# pcb-lt3032.net
KiCad netlist of a schematic drawn in EAGLE
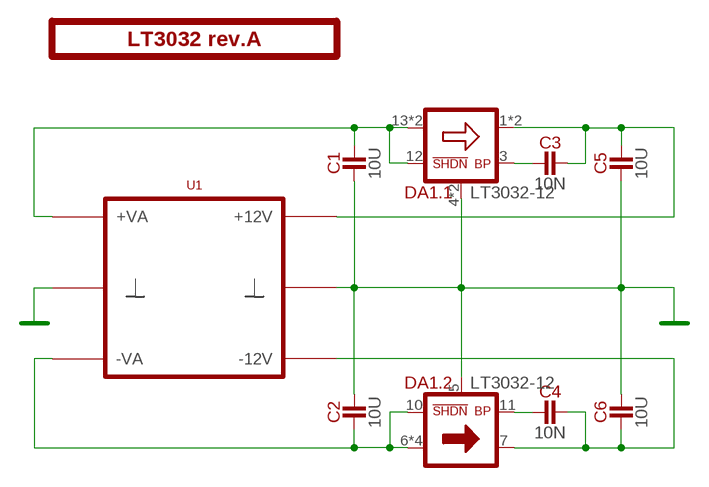
[diagram p0: schematic, sheet 1]

(export (version "E")
  (design (tool "Eeschema 10.0.6"))
  (components
    (comp (ref "C1")
      (value "10U")
      (footprint "eagle-import:C-1206")
      (libsource (lib "eagle-import") (part "?10U"))
    )
    (comp (ref "C2")
      (value "10U")
      (footprint "eagle-import:C-1206")
      (libsource (lib "eagle-import") (part "?10U"))
    )
    (comp (ref "C3")
      (value "10N")
      (footprint "eagle-import:C-0805")
      (libsource (lib "eagle-import") (part "?10N"))
    )
    (comp (ref "C4")
      (value "10N")
      (footprint "eagle-import:C-0805")
      (libsource (lib "eagle-import") (part "?10N"))
    )
    (comp (ref "C5")
      (value "10U")
      (footprint "eagle-import:C-1206")
      (libsource (lib "eagle-import") (part "?10U"))
    )
    (comp (ref "C6")
      (value "10U")
      (footprint "eagle-import:C-1206")
      (libsource (lib "eagle-import") (part "?10U"))
    )
    (comp (ref "DA1")
      (value "LT3032-12")
      (footprint "eagle-import:DE14MA")
      (libsource (lib "eagle-import") (part "LT3032-12"))
    )
    (comp (ref "PCB1")
      (value "LT3032 rev.A")
      (footprint "eagle-import:F-LOGO")
      (libsource (lib "eagle-import") (part "GENERIC-LOGO"))
    )
    (comp (ref "U1")
      (value "F-DUAL-SUPPLY-BOARD")
      (footprint "eagle-import:F-DIP8-HEATSINK-NOSILK")
      (libsource (lib "eagle-import") (part "F-DUAL-SUPPLY-BOARD"))
    )
  )
  (nets
    (net (code "1") (name "GND") (class "Default")
      (node (ref "C1") (pin "1") (pinfunction "1_1") (pintype "passive"))
      (node (ref "C2") (pin "2") (pinfunction "2_2") (pintype "passive"))
      (node (ref "C5") (pin "1") (pinfunction "1_1") (pintype "passive"))
      (node (ref "C6") (pin "2") (pinfunction "2_2") (pintype "passive"))
      (node (ref "DA1") (pin "15") (pinfunction "GND_15") (pintype "passive"))
      (node (ref "DA1") (pin "4") (pinfunction "GND_4") (pintype "passive"))
      (node (ref "DA1") (pin "5") (pinfunction "GND_5") (pintype "passive"))
      (node (ref "U1") (pin "2") (pinfunction "GND1_2") (pintype "bidirectional"))
      (node (ref "U1") (pin "3") (pinfunction "GND1_3") (pintype "bidirectional"))
      (node (ref "U1") (pin "6") (pinfunction "GND_6") (pintype "bidirectional"))
      (node (ref "U1") (pin "7") (pinfunction "GND_7") (pintype "bidirectional"))
      (node (ref "U1") (pin "P$1") (pinfunction "GND_P$1") (pintype "bidirectional"))
    )
    (net (code "2") (name "Net-(DA1A-BYP)") (class "Default")
      (node (ref "C3") (pin "1") (pinfunction "1_1") (pintype "passive"))
      (node (ref "DA1") (pin "3") (pinfunction "BYP_3") (pintype "passive"))
    )
    (net (code "3") (name "Net-(DA1A-~{SHDN})") (class "Default")
      (node (ref "C1") (pin "2") (pinfunction "2_2") (pintype "passive"))
      (node (ref "DA1") (pin "12") (pinfunction "~{SHDN}_12") (pintype "passive"))
      (node (ref "DA1") (pin "13") (pinfunction "IN_13") (pintype "passive"))
      (node (ref "DA1") (pin "14") (pinfunction "IN_14") (pintype "passive"))
      (node (ref "U1") (pin "1") (pinfunction "P+VA_1") (pintype "bidirectional"))
    )
    (net (code "4") (name "Net-(DA1B-BYP)") (class "Default")
      (node (ref "C4") (pin "1") (pinfunction "1_1") (pintype "passive"))
      (node (ref "DA1") (pin "11") (pinfunction "BYP_11") (pintype "passive"))
    )
    (net (code "5") (name "Net-(DA1B-OUT)") (class "Default")
      (node (ref "C4") (pin "2") (pinfunction "2_2") (pintype "passive"))
      (node (ref "C6") (pin "1") (pinfunction "1_1") (pintype "passive"))
      (node (ref "DA1") (pin "7") (pinfunction "OUT_7") (pintype "passive"))
      (node (ref "U1") (pin "5") (pinfunction "P-12V_5") (pintype "bidirectional"))
    )
    (net (code "6") (name "Net-(DA1B-~{SHDN})") (class "Default")
      (node (ref "C2") (pin "1") (pinfunction "1_1") (pintype "passive"))
      (node (ref "DA1") (pin "10") (pinfunction "~{SHDN}_10") (pintype "passive"))
      (node (ref "DA1") (pin "16") (pinfunction "IN_16") (pintype "passive"))
      (node (ref "DA1") (pin "6") (pinfunction "IN_6") (pintype "passive"))
      (node (ref "DA1") (pin "8") (pinfunction "IN_8") (pintype "passive"))
      (node (ref "DA1") (pin "9") (pinfunction "IN_9") (pintype "passive"))
      (node (ref "U1") (pin "4") (pinfunction "P-VA_4") (pintype "bidirectional"))
    )
    (net (code "7") (name "Net-(U1-P+12V)") (class "Default")
      (node (ref "C3") (pin "2") (pinfunction "2_2") (pintype "passive"))
      (node (ref "C5") (pin "2") (pinfunction "2_2") (pintype "passive"))
      (node (ref "DA1") (pin "1") (pinfunction "OUT_1") (pintype "passive"))
      (node (ref "DA1") (pin "2") (pinfunction "OUT_2") (pintype "passive"))
      (node (ref "U1") (pin "8") (pinfunction "P+12V_8") (pintype "bidirectional"))
    )
  )
)
